# LT6018_breakout.net
KiCad netlist of a schematic drawn in Altium Designer
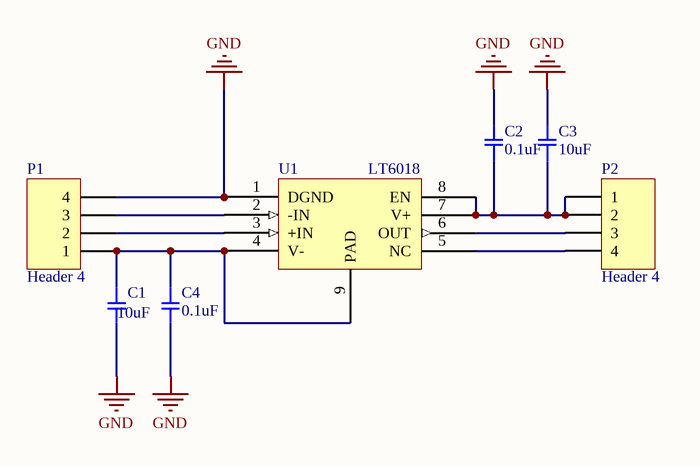
[diagram p0: LT6018_breakout.SchDoc]

(export (version "E")
  (design (tool "Eeschema 10.0.6"))
  (components
    (comp (ref "C1")
      (value "10uF")
      (footprint "SMD-0805C")
      (description "CAP CER 10000PF 250V X7T 0805")
      (fields
        (field (name "DIGI-KEY PART NUMBER") "490-13986-1-ND")
        (field (name "PART NUMBER") "GC321AD72E103KX01D")
      )
      (libsource (lib "capacitor_murata_0805") (part "GC321AD72E103KX01D"))
    )
    (comp (ref "C2")
      (value "0.1uF")
      (footprint "SMD-0805C")
      (description "CAP CER 10000PF 250V X7T 0805")
      (fields
        (field (name "DIGI-KEY PART NUMBER") "490-13986-1-ND")
        (field (name "PART NUMBER") "GC321AD72E103KX01D")
      )
      (libsource (lib "capacitor_murata_0805") (part "GC321AD72E103KX01D"))
    )
    (comp (ref "C3")
      (value "10uF")
      (footprint "SMD-0805C")
      (description "CAP CER 10000PF 250V X7T 0805")
      (fields
        (field (name "DIGI-KEY PART NUMBER") "490-13986-1-ND")
        (field (name "PART NUMBER") "GC321AD72E103KX01D")
      )
      (libsource (lib "capacitor_murata_0805") (part "GC321AD72E103KX01D"))
    )
    (comp (ref "C4")
      (value "0.1uF")
      (footprint "SMD-0805C")
      (description "CAP CER 10000PF 250V X7T 0805")
      (fields
        (field (name "DIGI-KEY PART NUMBER") "490-13986-1-ND")
        (field (name "PART NUMBER") "GC321AD72E103KX01D")
      )
      (libsource (lib "capacitor_murata_0805") (part "GC321AD72E103KX01D"))
    )
    (comp (ref "P1")
      (value "Header 4")
      (footprint "HDR1X4")
      (description "Header, 4-Pin")
      (fields (field (name "PUBLISHER") "Altium Limited"))
      (libsource (lib "") (part "Header 4_1"))
    )
    (comp (ref "P2")
      (value "Header 4")
      (footprint "HDR1X4")
      (description "Header, 4-Pin")
      (fields (field (name "PUBLISHER") "Altium Limited"))
      (libsource (lib "Miscellaneous Connectors") (part "Header 4"))
    )
    (comp (ref "U1") (value "LT6018") (footprint "LT6018") (libsource (lib "LT6018") (part "LT6018")))
  )
  (nets
    (net (code "1") (name "GND") (class "Default")
      (node (ref "C1") (pin "2") (pinfunction "2_2") (pintype "passive"))
      (node (ref "C2") (pin "2") (pinfunction "2_2") (pintype "passive"))
      (node (ref "C3") (pin "2") (pinfunction "2_2") (pintype "passive"))
      (node (ref "C4") (pin "2") (pinfunction "2_2") (pintype "passive"))
      (node (ref "P1") (pin "4") (pinfunction "4_4") (pintype "passive"))
      (node (ref "U1") (pin "1") (pinfunction "DGND_1") (pintype "power_in"))
    )
    (net (code "2") (name "Net-(U1-+IN)") (class "Default")
      (node (ref "P1") (pin "2") (pinfunction "2_2") (pintype "passive"))
      (node (ref "U1") (pin "3") (pinfunction "+IN_3") (pintype "input"))
    )
    (net (code "3") (name "Net-(U1--IN)") (class "Default")
      (node (ref "P1") (pin "3") (pinfunction "3_3") (pintype "passive"))
      (node (ref "U1") (pin "2") (pinfunction "-IN_2") (pintype "input"))
    )
    (net (code "4") (name "Net-(U1-EN)") (class "Default")
      (node (ref "C2") (pin "1") (pinfunction "1_1") (pintype "passive"))
      (node (ref "C3") (pin "1") (pinfunction "1_1") (pintype "passive"))
      (node (ref "P2") (pin "1") (pinfunction "1_1") (pintype "passive"))
      (node (ref "P2") (pin "2") (pinfunction "2_2") (pintype "passive"))
      (node (ref "U1") (pin "7") (pinfunction "V+_7") (pintype "power_in"))
      (node (ref "U1") (pin "8") (pinfunction "EN_8") (pintype "passive"))
    )
    (net (code "5") (name "Net-(U1-NC)") (class "Default")
      (node (ref "P2") (pin "4") (pinfunction "4_4") (pintype "passive"))
      (node (ref "U1") (pin "5") (pinfunction "NC_5") (pintype "passive"))
    )
    (net (code "6") (name "Net-(U1-OUT)") (class "Default")
      (node (ref "P2") (pin "3") (pinfunction "3_3") (pintype "passive"))
      (node (ref "U1") (pin "6") (pinfunction "OUT_6") (pintype "output"))
    )
    (net (code "7") (name "Net-(U1-PAD)") (class "Default")
      (node (ref "C1") (pin "1") (pinfunction "1_1") (pintype "passive"))
      (node (ref "C4") (pin "1") (pinfunction "1_1") (pintype "passive"))
      (node (ref "P1") (pin "1") (pinfunction "1_1") (pintype "passive"))
      (node (ref "U1") (pin "4") (pinfunction "V-_4") (pintype "power_in"))
      (node (ref "U1") (pin "9") (pinfunction "PAD_9") (pintype "passive"))
    )
  )
)
